# schematic.net
KiCad netlist of a schematic drawn in Altium Designer
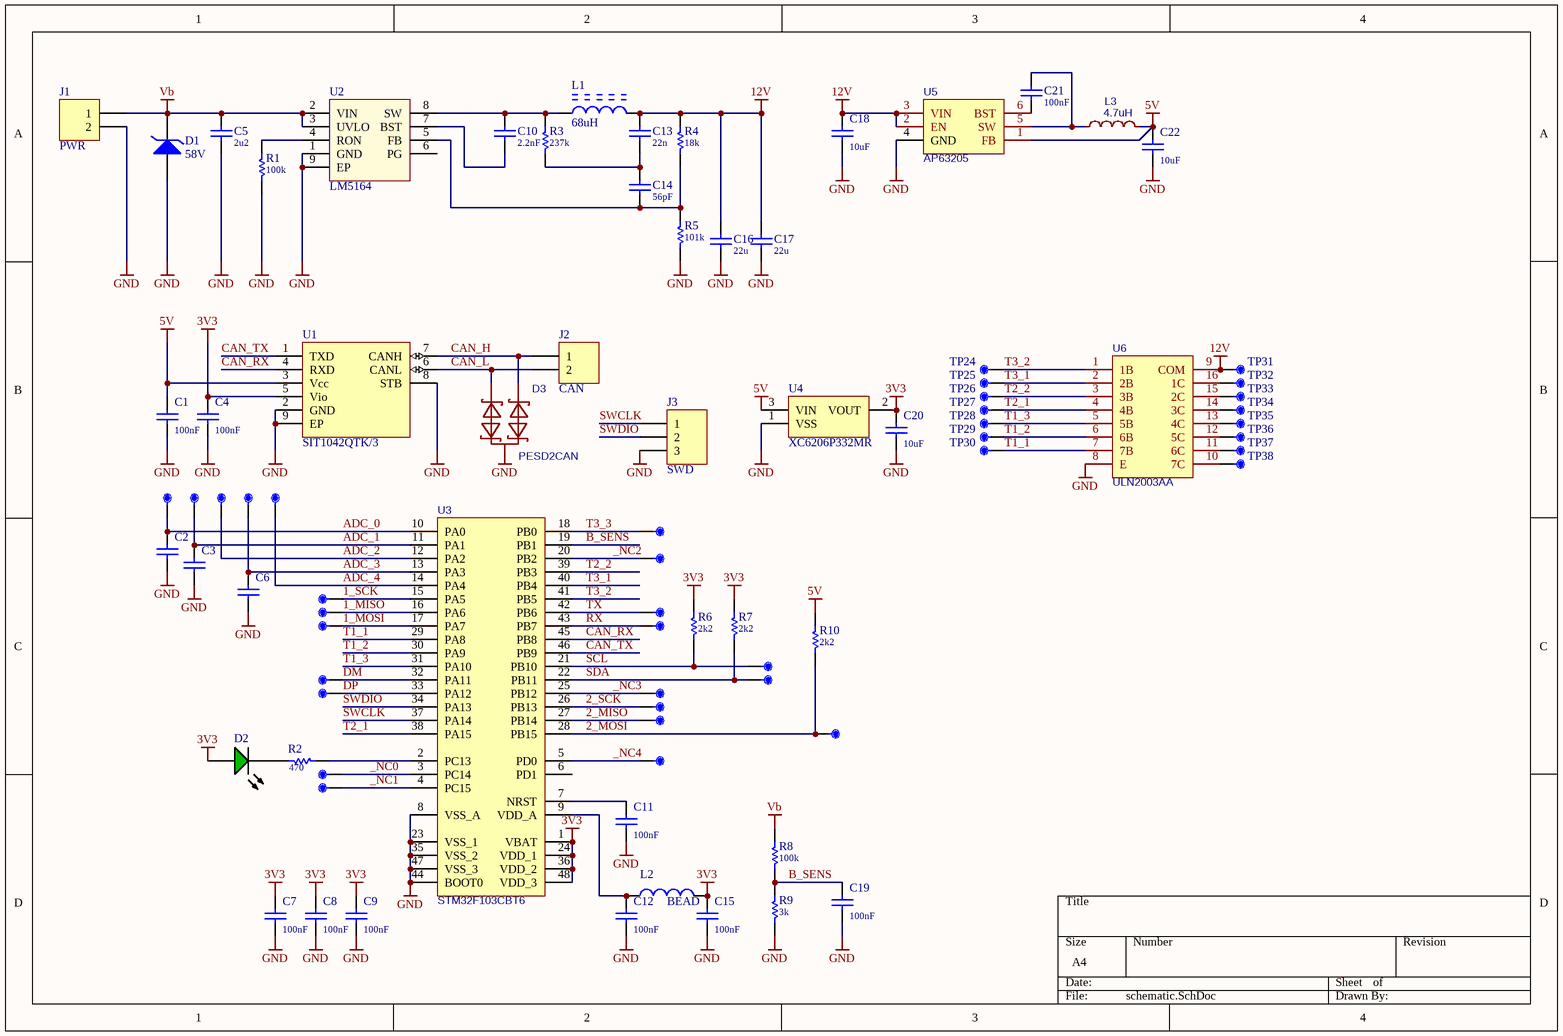
[diagram p0: schematic.SchDoc]

(export (version "E")
  (design (tool "Eeschema 10.0.6"))
  (components
    (comp (ref "C1")
      (value "100nF")
      (footprint "C0402")
      (description "100nF 50V 0402")
      (libsource (lib "Miscellaneous Devices") (part "CAP"))
    )
    (comp (ref "C2")
      (value "100nF")
      (footprint "C0402")
      (description "100nF 50V 0402")
      (libsource (lib "Miscellaneous Devices") (part "CAP"))
    )
    (comp (ref "C3")
      (value "100nF")
      (footprint "C0402")
      (description "100nF 50V 0402")
      (libsource (lib "Miscellaneous Devices") (part "CAP"))
    )
    (comp (ref "C4")
      (value "100nF")
      (footprint "C0402")
      (description "100nF 50V 0402")
      (libsource (lib "Miscellaneous Devices") (part "CAP"))
    )
    (comp (ref "C5")
      (value "2u2")
      (footprint "C1210")
      (description "2.2uF 100V 1210")
      (libsource (lib "Miscellaneous Devices") (part "CAP"))
    )
    (comp (ref "C6")
      (value "100nF")
      (footprint "C0402")
      (description "100nF 50V 0402")
      (libsource (lib "Miscellaneous Devices") (part "CAP"))
    )
    (comp (ref "C7")
      (value "100nF")
      (footprint "C0402")
      (description "100nF 50V 0402")
      (libsource (lib "Miscellaneous Devices") (part "CAP"))
    )
    (comp (ref "C8")
      (value "100nF")
      (footprint "C0402")
      (description "100nF 50V 0402")
      (libsource (lib "Miscellaneous Devices") (part "CAP"))
    )
    (comp (ref "C9")
      (value "100nF")
      (footprint "C0402")
      (description "100nF 50V 0402")
      (libsource (lib "Miscellaneous Devices") (part "CAP"))
    )
    (comp (ref "C10")
      (value "2.2nF")
      (footprint "C0603")
      (description "2.2nF 50V 0603")
      (libsource (lib "Miscellaneous Devices") (part "CAP"))
    )
    (comp (ref "C11")
      (value "100nF")
      (footprint "C0402")
      (description "100nF 50V 0402")
      (libsource (lib "Miscellaneous Devices") (part "CAP"))
    )
    (comp (ref "C12")
      (value "100nF")
      (footprint "C0402")
      (description "100nF 50V 0402")
      (libsource (lib "Miscellaneous Devices") (part "CAP"))
    )
    (comp (ref "C13")
      (value "22n")
      (footprint "C0603")
      (description "2.2nF 0603")
      (libsource (lib "Miscellaneous Devices") (part "CAP"))
    )
    (comp (ref "C14")
      (value "56pF")
      (footprint "C0603")
      (description "56pF 0603")
      (libsource (lib "Miscellaneous Devices") (part "CAP"))
    )
    (comp (ref "C15")
      (value "100nF")
      (footprint "C0402")
      (description "100nF 50V 0402")
      (libsource (lib "Miscellaneous Devices") (part "CAP"))
    )
    (comp (ref "C16")
      (value "22u")
      (footprint "C1210")
      (description "22u 35V 1210")
      (libsource (lib "Miscellaneous Devices") (part "CAP"))
    )
    (comp (ref "C17")
      (value "22u")
      (footprint "C1210")
      (description "22u 35V 1210")
      (libsource (lib "Miscellaneous Devices") (part "CAP"))
    )
    (comp (ref "C18")
      (value "10uF")
      (footprint "C1206")
      (description "10uf 50V 1206")
      (fields (field (name "LCSC PART NUMBER") "C89632"))
      (libsource (lib "Miscellaneous Devices") (part "CAP"))
    )
    (comp (ref "C19")
      (value "100nF")
      (footprint "C0402")
      (description "100nF 50V 0402")
      (libsource (lib "Miscellaneous Devices") (part "CAP"))
    )
    (comp (ref "C20")
      (value "10uF")
      (footprint "C0603")
      (description "10uf 50V 1206")
      (libsource (lib "Miscellaneous Devices") (part "CAP"))
    )
    (comp (ref "C21")
      (value "100nF")
      (footprint "C0402")
      (description "100nF 50V 0402")
      (libsource (lib "Miscellaneous Devices") (part "CAP"))
    )
    (comp (ref "C22")
      (value "10uF")
      (footprint "C1206")
      (description "10uf 50V 1206")
      (fields (field (name "LCSC PART NUMBER") "C89632"))
      (libsource (lib "Miscellaneous Devices") (part "CAP"))
    )
    (comp (ref "D1")
      (value "58V")
      (footprint "SMA")
      (description "SMAJ58A")
      (fields (field (name "LCSC PART NUMBER") "C693617"))
      (libsource (lib "Miscellaneous Devices") (part "NCP51460SN33T1G"))
    )
    (comp (ref "D2")
      (value "GRN")
      (footprint "LED-0603-GRN")
      (description "LED 0603 GRN")
      (libsource (lib "Miscellaneous Devices") (part "LED-0603-GREEN"))
    )
    (comp (ref "D3")
      (value "PESD2CAN")
      (footprint "SOT-23")
      (fields (field (name "LCSC PART NUMBER") "C5261081"))
      (libsource (lib "Miscellaneous Devices") (part "CDSOT23-SM712"))
    )
    (comp (ref "J1") (value "PWR") (footprint "HDR-1X2") (libsource (lib "Schlib1") (part "Header 2")))
    (comp (ref "J2") (value "CAN") (footprint "HDR-1X2") (libsource (lib "") (part "Header 2_1")))
    (comp (ref "J3")
      (value "SWD")
      (footprint "HDR-1x3-P1.25")
      (libsource (lib "Miscellaneous Devices") (part "Header 3"))
    )
    (comp (ref "L1")
      (value "68uH")
      (footprint "L0605-POWER")
      (description "PSPMAA0605H-680M-IGF")
      (libsource (lib "Miscellaneous Devices") (part "SRN3015-100M"))
    )
    (comp (ref "L2")
      (value "BEAD")
      (footprint "L0402")
      (description "BEAD 0402")
      (libsource (lib "Miscellaneous Devices") (part "BLM18AG601SN1D"))
    )
    (comp (ref "L3")
      (value "4.7uH")
      (footprint "IND-SMD_L4.4-W4.2")
      (fields (field (name "LCSC PART NUMBER") "C167208"))
      (libsource (lib "altium-import") (part "root_0_4.7uH_"))
    )
    (comp (ref "R1")
      (value "100k")
      (footprint "R0603")
      (description "100k 0603")
      (libsource (lib "Miscellaneous Devices") (part "RES"))
    )
    (comp (ref "R2")
      (value "470")
      (footprint "R0402")
      (description "470 0603")
      (libsource (lib "Miscellaneous Devices") (part "RES"))
    )
    (comp (ref "R3")
      (value "237k")
      (footprint "R0603")
      (description "237k 0603")
      (libsource (lib "Miscellaneous Devices") (part "RES"))
    )
    (comp (ref "R4")
      (value "18k")
      (footprint "R0603")
      (description "18k 1% 0603")
      (libsource (lib "Miscellaneous Devices") (part "RES"))
    )
    (comp (ref "R5")
      (value "101k")
      (footprint "R0603")
      (description "101k 0603")
      (libsource (lib "Miscellaneous Devices") (part "RES"))
    )
    (comp (ref "R6") (value "2k2") (footprint "R0402") (libsource (lib "Miscellaneous Devices") (part "RES")))
    (comp (ref "R7") (value "2k2") (footprint "R0402") (libsource (lib "Miscellaneous Devices") (part "RES")))
    (comp (ref "R8")
      (value "100k")
      (footprint "R0603")
      (libsource (lib "Miscellaneous Devices") (part "RES"))
    )
    (comp (ref "R9") (value "3k") (footprint "R0603") (libsource (lib "Miscellaneous Devices") (part "RES")))
    (comp (ref "R10")
      (value "2k2")
      (footprint "R0402")
      (libsource (lib "Miscellaneous Devices") (part "RES"))
    )
    (comp (ref "TP1")
      (value "~")
      (footprint "TP_THT")
      (libsource (lib "Miscellaneous Devices") (part "TP_Dup1"))
    )
    (comp (ref "TP2")
      (value "~")
      (footprint "TP_THT")
      (libsource (lib "Miscellaneous Devices") (part "TP_Dup1"))
    )
    (comp (ref "TP3")
      (value "~")
      (footprint "TP_THT")
      (libsource (lib "Miscellaneous Devices") (part "TP_Dup1"))
    )
    (comp (ref "TP4")
      (value "~")
      (footprint "TP_THT")
      (libsource (lib "Miscellaneous Devices") (part "TP_Dup1"))
    )
    (comp (ref "TP5")
      (value "~")
      (footprint "TP_THT")
      (libsource (lib "Miscellaneous Devices") (part "TP_Dup1"))
    )
    (comp (ref "TP6")
      (value "~")
      (footprint "TP_THT")
      (libsource (lib "Miscellaneous Devices") (part "TP_Dup1"))
    )
    (comp (ref "TP7")
      (value "~")
      (footprint "TP_THT")
      (libsource (lib "Miscellaneous Devices") (part "TP_Dup1"))
    )
    (comp (ref "TP8")
      (value "~")
      (footprint "TP_THT")
      (libsource (lib "Miscellaneous Devices") (part "TP_Dup1"))
    )
    (comp (ref "TP9")
      (value "~")
      (footprint "TP_THT")
      (libsource (lib "Miscellaneous Devices") (part "TP_Dup1"))
    )
    (comp (ref "TP10")
      (value "~")
      (footprint "TP_THT")
      (libsource (lib "Miscellaneous Devices") (part "TP_Dup1"))
    )
    (comp (ref "TP11")
      (value "~")
      (footprint "TP_THT")
      (libsource (lib "Miscellaneous Devices") (part "TP_Dup1"))
    )
    (comp (ref "TP12")
      (value "~")
      (footprint "TP_THT")
      (libsource (lib "Miscellaneous Devices") (part "TP_Dup1"))
    )
    (comp (ref "TP13")
      (value "~")
      (footprint "TP_THT")
      (libsource (lib "Miscellaneous Devices") (part "TP_Dup1"))
    )
    (comp (ref "TP14")
      (value "~")
      (footprint "TP_THT")
      (libsource (lib "Miscellaneous Devices") (part "TP_Dup1"))
    )
    (comp (ref "TP15")
      (value "~")
      (footprint "TP_THT")
      (libsource (lib "Miscellaneous Devices") (part "TP_Dup1"))
    )
    (comp (ref "TP16")
      (value "~")
      (footprint "TP_THT")
      (libsource (lib "Miscellaneous Devices") (part "TP_Dup1"))
    )
    (comp (ref "TP17")
      (value "~")
      (footprint "TP_THT")
      (libsource (lib "Miscellaneous Devices") (part "TP_Dup1"))
    )
    (comp (ref "TP18")
      (value "~")
      (footprint "TP_THT")
      (libsource (lib "Miscellaneous Devices") (part "TP_Dup1"))
    )
    (comp (ref "TP19")
      (value "~")
      (footprint "TP_THT")
      (libsource (lib "Miscellaneous Devices") (part "TP_Dup1"))
    )
    (comp (ref "TP20")
      (value "~")
      (footprint "TP_THT")
      (libsource (lib "Miscellaneous Devices") (part "TP_Dup1"))
    )
    (comp (ref "TP21")
      (value "~")
      (footprint "TP_THT")
      (libsource (lib "Miscellaneous Devices") (part "TP_Dup1"))
    )
    (comp (ref "TP22")
      (value "~")
      (footprint "TP_THT")
      (libsource (lib "Miscellaneous Devices") (part "TP_Dup1"))
    )
    (comp (ref "TP23")
      (value "~")
      (footprint "TP_THT")
      (libsource (lib "Miscellaneous Devices") (part "TP_Dup1"))
    )
    (comp (ref "TP24")
      (value "~")
      (footprint "TP_THT")
      (libsource (lib "Miscellaneous Devices") (part "TP_Dup1"))
    )
    (comp (ref "TP25")
      (value "~")
      (footprint "TP_THT")
      (libsource (lib "Miscellaneous Devices") (part "TP_Dup1"))
    )
    (comp (ref "TP26")
      (value "~")
      (footprint "TP_THT")
      (libsource (lib "Miscellaneous Devices") (part "TP_Dup1"))
    )
    (comp (ref "TP27")
      (value "~")
      (footprint "TP_THT")
      (libsource (lib "Miscellaneous Devices") (part "TP_Dup1"))
    )
    (comp (ref "TP28")
      (value "~")
      (footprint "TP_THT")
      (libsource (lib "Miscellaneous Devices") (part "TP_Dup1"))
    )
    (comp (ref "TP29")
      (value "~")
      (footprint "TP_THT")
      (libsource (lib "Miscellaneous Devices") (part "TP_Dup1"))
    )
    (comp (ref "TP30")
      (value "~")
      (footprint "TP_THT")
      (libsource (lib "Miscellaneous Devices") (part "TP_Dup1"))
    )
    (comp (ref "TP31")
      (value "~")
      (footprint "TP_THT")
      (libsource (lib "Miscellaneous Devices") (part "TP_Dup1"))
    )
    (comp (ref "TP32")
      (value "~")
      (footprint "TP_THT")
      (libsource (lib "Miscellaneous Devices") (part "TP_Dup1"))
    )
    (comp (ref "TP33")
      (value "~")
      (footprint "TP_THT")
      (libsource (lib "Miscellaneous Devices") (part "TP_Dup1"))
    )
    (comp (ref "TP34")
      (value "~")
      (footprint "TP_THT")
      (libsource (lib "Miscellaneous Devices") (part "TP_Dup1"))
    )
    (comp (ref "TP35")
      (value "~")
      (footprint "TP_THT")
      (libsource (lib "Miscellaneous Devices") (part "TP_Dup1"))
    )
    (comp (ref "TP36")
      (value "~")
      (footprint "TP_THT")
      (libsource (lib "Miscellaneous Devices") (part "TP_Dup1"))
    )
    (comp (ref "TP37")
      (value "~")
      (footprint "TP_THT")
      (libsource (lib "Miscellaneous Devices") (part "TP_Dup1"))
    )
    (comp (ref "TP38")
      (value "~")
      (footprint "TP_THT")
      (libsource (lib "Miscellaneous Devices") (part "TP_Dup1"))
    )
    (comp (ref "U1")
      (value "SIT1042QTK/3")
      (footprint "DFN8_3X3_P065")
      (description "IC INTERFACE CAN")
      (libsource (lib "Miscellaneous Devices") (part "LTC2875"))
    )
    (comp (ref "U2") (value "LM5164") (footprint "PowerSOIC-8") (libsource (lib "Schlib2") (part "LM5164")))
    (comp (ref "U3")
      (value "STM32F103CBT6")
      (footprint "LQFP-48")
      (libsource (lib "Schlib1") (part "STM32F103CBT6"))
    )
    (comp (ref "U4")
      (value "XC6206P332MR")
      (footprint "SOT-23")
      (libsource (lib "Schlib1") (part "Component_4_1"))
    )
    (comp (ref "U5")
      (value "AP63205")
      (footprint "SOT-23-6")
      (fields (field (name "LCSC PART NUMBER") "C780769"))
      (libsource (lib "Schlib1") (part "AP63203WU-7"))
    )
    (comp (ref "U6") (value "ULN2003AA") (footprint "SOIC-16") (libsource (lib "Schlib1") (part "ULN2003A")))
  )
  (nets
    (net (code "1") (name "/1_MISO") (class "Default")
      (node (ref "TP7") (pin "1") (pinfunction "1_1") (pintype "passive"))
      (node (ref "U3") (pin "16") (pinfunction "PA6_16") (pintype "passive"))
    )
    (net (code "2") (name "/1_MOSI") (class "Default")
      (node (ref "TP8") (pin "1") (pinfunction "1_1") (pintype "passive"))
      (node (ref "U3") (pin "17") (pinfunction "PA7_17") (pintype "passive"))
    )
    (net (code "3") (name "/1_SCK") (class "Default")
      (node (ref "TP6") (pin "1") (pinfunction "1_1") (pintype "passive"))
      (node (ref "U3") (pin "15") (pinfunction "PA5_15") (pintype "passive"))
    )
    (net (code "4") (name "/2_MISO") (class "Default")
      (node (ref "TP19") (pin "1") (pinfunction "1_1") (pintype "passive"))
      (node (ref "U3") (pin "27") (pinfunction "PB14_27") (pintype "passive"))
    )
    (net (code "5") (name "/2_MOSI") (class "Default")
      (node (ref "R10") (pin "1") (pinfunction "1_1") (pintype "passive"))
      (node (ref "TP23") (pin "1") (pinfunction "1_1") (pintype "passive"))
      (node (ref "U3") (pin "28") (pinfunction "PB15_28") (pintype "passive"))
    )
    (net (code "6") (name "/2_SCK") (class "Default")
      (node (ref "TP18") (pin "1") (pinfunction "1_1") (pintype "passive"))
      (node (ref "U3") (pin "26") (pinfunction "PB13_26") (pintype "passive"))
    )
    (net (code "7") (name "/ADC_0") (class "Default")
      (node (ref "C2") (pin "2") (pinfunction "2_2") (pintype "passive"))
      (node (ref "TP1") (pin "1") (pinfunction "1_1") (pintype "passive"))
      (node (ref "U3") (pin "10") (pinfunction "PA0_10") (pintype "passive"))
    )
    (net (code "8") (name "/ADC_1") (class "Default")
      (node (ref "C3") (pin "2") (pinfunction "2_2") (pintype "passive"))
      (node (ref "TP2") (pin "1") (pinfunction "1_1") (pintype "passive"))
      (node (ref "U3") (pin "11") (pinfunction "PA1_11") (pintype "passive"))
    )
    (net (code "9") (name "/ADC_2") (class "Default")
      (node (ref "TP3") (pin "1") (pinfunction "1_1") (pintype "passive"))
      (node (ref "U3") (pin "12") (pinfunction "PA2_12") (pintype "passive"))
    )
    (net (code "10") (name "/ADC_3") (class "Default")
      (node (ref "C6") (pin "2") (pinfunction "2_2") (pintype "passive"))
      (node (ref "TP4") (pin "1") (pinfunction "1_1") (pintype "passive"))
      (node (ref "U3") (pin "13") (pinfunction "PA3_13") (pintype "passive"))
    )
    (net (code "11") (name "/ADC_4") (class "Default")
      (node (ref "TP5") (pin "1") (pinfunction "1_1") (pintype "passive"))
      (node (ref "U3") (pin "14") (pinfunction "PA4_14") (pintype "passive"))
    )
    (net (code "12") (name "/B_SENS") (class "Default")
      (node (ref "C19") (pin "2") (pinfunction "2_2") (pintype "passive"))
      (node (ref "R8") (pin "1") (pinfunction "1_1") (pintype "passive"))
      (node (ref "R9") (pin "2") (pinfunction "2_2") (pintype "passive"))
      (node (ref "U3") (pin "19") (pinfunction "PB1_19") (pintype "passive"))
    )
    (net (code "13") (name "/CAN_H") (class "Default")
      (node (ref "D3") (pin "2") (pinfunction "2_2") (pintype "passive"))
      (node (ref "J2") (pin "1") (pinfunction "1_1") (pintype "passive"))
      (node (ref "U1") (pin "7") (pinfunction "CANH_7") (pintype "bidirectional"))
    )
    (net (code "14") (name "/CAN_L") (class "Default")
      (node (ref "D3") (pin "1") (pinfunction "1_1") (pintype "passive"))
      (node (ref "J2") (pin "2") (pinfunction "2_2") (pintype "passive"))
      (node (ref "U1") (pin "6") (pinfunction "CANL_6") (pintype "bidirectional"))
    )
    (net (code "15") (name "/CAN_RX") (class "Default")
      (node (ref "U1") (pin "4") (pinfunction "RXD_4") (pintype "passive"))
      (node (ref "U3") (pin "45") (pinfunction "PB8_45") (pintype "passive"))
    )
    (net (code "16") (name "/CAN_TX") (class "Default")
      (node (ref "U1") (pin "1") (pinfunction "TXD_1") (pintype "passive"))
      (node (ref "U3") (pin "46") (pinfunction "PB9_46") (pintype "passive"))
    )
    (net (code "17") (name "/DM") (class "Default")
      (node (ref "TP9") (pin "1") (pinfunction "1_1") (pintype "passive"))
      (node (ref "U3") (pin "32") (pinfunction "PA11_32") (pintype "passive"))
    )
    (net (code "18") (name "/DP") (class "Default")
      (node (ref "TP10") (pin "1") (pinfunction "1_1") (pintype "passive"))
      (node (ref "U3") (pin "33") (pinfunction "PA12_33") (pintype "passive"))
    )
    (net (code "19") (name "/RX") (class "Default")
      (node (ref "TP16") (pin "1") (pinfunction "1_1") (pintype "passive"))
      (node (ref "U3") (pin "43") (pinfunction "PB7_43") (pintype "passive"))
    )
    (net (code "20") (name "/SCL") (class "Default")
      (node (ref "R6") (pin "1") (pinfunction "1_1") (pintype "passive"))
      (node (ref "TP21") (pin "1") (pinfunction "1_1") (pintype "passive"))
      (node (ref "U3") (pin "21") (pinfunction "PB10_21") (pintype "passive"))
    )
    (net (code "21") (name "/SDA") (class "Default")
      (node (ref "R7") (pin "1") (pinfunction "1_1") (pintype "passive"))
      (node (ref "TP22") (pin "1") (pinfunction "1_1") (pintype "passive"))
      (node (ref "U3") (pin "22") (pinfunction "PB11_22") (pintype "passive"))
    )
    (net (code "22") (name "/SWCLK") (class "Default")
      (node (ref "J3") (pin "1") (pinfunction "1_1") (pintype "passive"))
      (node (ref "U3") (pin "37") (pinfunction "PA14_37") (pintype "passive"))
    )
    (net (code "23") (name "/SWDIO") (class "Default")
      (node (ref "J3") (pin "2") (pinfunction "2_2") (pintype "passive"))
      (node (ref "U3") (pin "34") (pinfunction "PA13_34") (pintype "passive"))
    )
    (net (code "24") (name "/T1_1") (class "Default")
      (node (ref "TP30") (pin "1") (pinfunction "1_1") (pintype "passive"))
      (node (ref "U3") (pin "29") (pinfunction "PA8_29") (pintype "passive"))
      (node (ref "U6") (pin "7") (pinfunction "7B_7") (pintype "passive"))
    )
    (net (code "25") (name "/T1_2") (class "Default")
      (node (ref "TP29") (pin "1") (pinfunction "1_1") (pintype "passive"))
      (node (ref "U3") (pin "30") (pinfunction "PA9_30") (pintype "passive"))
      (node (ref "U6") (pin "6") (pinfunction "6B_6") (pintype "passive"))
    )
    (net (code "26") (name "/T1_3") (class "Default")
      (node (ref "TP28") (pin "1") (pinfunction "1_1") (pintype "passive"))
      (node (ref "U3") (pin "31") (pinfunction "PA10_31") (pintype "passive"))
      (node (ref "U6") (pin "5") (pinfunction "5B_5") (pintype "passive"))
    )
    (net (code "27") (name "/T2_1") (class "Default")
      (node (ref "TP27") (pin "1") (pinfunction "1_1") (pintype "passive"))
      (node (ref "U3") (pin "38") (pinfunction "PA15_38") (pintype "passive"))
      (node (ref "U6") (pin "4") (pinfunction "4B_4") (pintype "passive"))
    )
    (net (code "28") (name "/T2_2") (class "Default")
      (node (ref "TP26") (pin "1") (pinfunction "1_1") (pintype "passive"))
      (node (ref "U3") (pin "39") (pinfunction "PB3_39") (pintype "passive"))
      (node (ref "U6") (pin "3") (pinfunction "3B_3") (pintype "passive"))
    )
    (net (code "29") (name "/T3_1") (class "Default")
      (node (ref "TP25") (pin "1") (pinfunction "1_1") (pintype "passive"))
      (node (ref "U3") (pin "40") (pinfunction "PB4_40") (pintype "passive"))
      (node (ref "U6") (pin "2") (pinfunction "2B_2") (pintype "passive"))
    )
    (net (code "30") (name "/T3_2") (class "Default")
      (node (ref "TP24") (pin "1") (pinfunction "1_1") (pintype "passive"))
      (node (ref "U3") (pin "41") (pinfunction "PB5_41") (pintype "passive"))
      (node (ref "U6") (pin "1") (pinfunction "1B_1") (pintype "passive"))
    )
    (net (code "31") (name "/T3_3") (class "Default")
      (node (ref "TP13") (pin "1") (pinfunction "1_1") (pintype "passive"))
      (node (ref "U3") (pin "18") (pinfunction "PB0_18") (pintype "passive"))
    )
    (net (code "32") (name "/TX") (class "Default")
      (node (ref "TP15") (pin "1") (pinfunction "1_1") (pintype "passive"))
      (node (ref "U3") (pin "42") (pinfunction "PB6_42") (pintype "passive"))
    )
    (net (code "33") (name "/_NC0") (class "Default")
      (node (ref "TP11") (pin "1") (pinfunction "1_1") (pintype "passive"))
      (node (ref "U3") (pin "3") (pinfunction "PC14_3") (pintype "passive"))
    )
    (net (code "34") (name "/_NC1") (class "Default")
      (node (ref "TP12") (pin "1") (pinfunction "1_1") (pintype "passive"))
      (node (ref "U3") (pin "4") (pinfunction "PC15_4") (pintype "passive"))
    )
    (net (code "35") (name "/_NC2") (class "Default")
      (node (ref "TP14") (pin "1") (pinfunction "1_1") (pintype "passive"))
      (node (ref "U3") (pin "20") (pinfunction "PB2_20") (pintype "passive"))
    )
    (net (code "36") (name "/_NC3") (class "Default")
      (node (ref "TP17") (pin "1") (pinfunction "1_1") (pintype "passive"))
      (node (ref "U3") (pin "25") (pinfunction "PB12_25") (pintype "passive"))
    )
    (net (code "37") (name "/_NC4") (class "Default")
      (node (ref "TP20") (pin "1") (pinfunction "1_1") (pintype "passive"))
      (node (ref "U3") (pin "5") (pinfunction "PD0_5") (pintype "passive"))
    )
    (net (code "38") (name "3V3") (class "Default")
      (node (ref "C15") (pin "2") (pinfunction "2_2") (pintype "passive"))
      (node (ref "C20") (pin "2") (pinfunction "2_2") (pintype "passive"))
      (node (ref "C4") (pin "2") (pinfunction "2_2") (pintype "passive"))
      (node (ref "C7") (pin "2") (pinfunction "2_2") (pintype "passive"))
      (node (ref "C8") (pin "2") (pinfunction "2_2") (pintype "passive"))
      (node (ref "C9") (pin "2") (pinfunction "2_2") (pintype "passive"))
      (node (ref "D2") (pin "1") (pinfunction "A_1") (pintype "passive"))
      (node (ref "L2") (pin "1") (pinfunction "1_1") (pintype "passive"))
      (node (ref "R6") (pin "2") (pinfunction "2_2") (pintype "passive"))
      (node (ref "R7") (pin "2") (pinfunction "2_2") (pintype "passive"))
      (node (ref "U1") (pin "5") (pinfunction "Vio_5") (pintype "passive"))
      (node (ref "U3") (pin "1") (pinfunction "VBAT_1") (pintype "passive"))
      (node (ref "U3") (pin "24") (pinfunction "VDD_1_24") (pintype "passive"))
      (node (ref "U3") (pin "36") (pinfunction "VDD_2_36") (pintype "passive"))
      (node (ref "U3") (pin "48") (pinfunction "VDD_3_48") (pintype "passive"))
      (node (ref "U4") (pin "2") (pinfunction "VOUT_2") (pintype "passive"))
    )
    (net (code "39") (name "5V") (class "Default")
      (node (ref "C1") (pin "2") (pinfunction "2_2") (pintype "passive"))
      (node (ref "C22") (pin "2") (pinfunction "2_2") (pintype "passive"))
      (node (ref "L3") (pin "2") (pinfunction "2_2") (pintype "passive"))
      (node (ref "R10") (pin "2") (pinfunction "2_2") (pintype "passive"))
      (node (ref "U1") (pin "3") (pinfunction "Vcc_3") (pintype "passive"))
      (node (ref "U4") (pin "3") (pinfunction "VIN_3") (pintype "passive"))
      (node (ref "U5") (pin "1") (pinfunction "FB_1") (pintype "passive"))
    )
    (net (code "40") (name "12V") (class "Default")
      (node (ref "C13") (pin "2") (pinfunction "2_2") (pintype "passive"))
      (node (ref "C16") (pin "2") (pinfunction "2_2") (pintype "passive"))
      (node (ref "C17") (pin "2") (pinfunction "2_2") (pintype "passive"))
      (node (ref "C18") (pin "2") (pinfunction "2_2") (pintype "passive"))
      (node (ref "L1") (pin "2") (pinfunction "2_2") (pintype "passive"))
      (node (ref "R4") (pin "1") (pinfunction "1_1") (pintype "passive"))
      (node (ref "TP31") (pin "1") (pinfunction "1_1") (pintype "passive"))
      (node (ref "U5") (pin "2") (pinfunction "EN_2") (pintype "passive"))
      (node (ref "U5") (pin "3") (pinfunction "VIN_3") (pintype "passive"))
      (node (ref "U6") (pin "9") (pinfunction "COM_9") (pintype "passive"))
    )
    (net (code "41") (name "GND") (class "Default")
      (node (ref "C1") (pin "1") (pinfunction "1_1") (pintype "passive"))
      (node (ref "C11") (pin "1") (pinfunction "1_1") (pintype "passive"))
      (node (ref "C12") (pin "1") (pinfunction "1_1") (pintype "passive"))
      (node (ref "C15") (pin "1") (pinfunction "1_1") (pintype "passive"))
      (node (ref "C16") (pin "1") (pinfunction "1_1") (pintype "passive"))
      (node (ref "C17") (pin "1") (pinfunction "1_1") (pintype "passive"))
      (node (ref "C18") (pin "1") (pinfunction "1_1") (pintype "passive"))
      (node (ref "C19") (pin "1") (pinfunction "1_1") (pintype "passive"))
      (node (ref "C2") (pin "1") (pinfunction "1_1") (pintype "passive"))
      (node (ref "C20") (pin "1") (pinfunction "1_1") (pintype "passive"))
      (node (ref "C22") (pin "1") (pinfunction "1_1") (pintype "passive"))
      (node (ref "C3") (pin "1") (pinfunction "1_1") (pintype "passive"))
      (node (ref "C4") (pin "1") (pinfunction "1_1") (pintype "passive"))
      (node (ref "C5") (pin "1") (pinfunction "1_1") (pintype "passive"))
      (node (ref "C6") (pin "1") (pinfunction "1_1") (pintype "passive"))
      (node (ref "C7") (pin "1") (pinfunction "1_1") (pintype "passive"))
      (node (ref "C8") (pin "1") (pinfunction "1_1") (pintype "passive"))
      (node (ref "C9") (pin "1") (pinfunction "1_1") (pintype "passive"))
      (node (ref "D1") (pin "1") (pinfunction "-_1") (pintype "passive"))
      (node (ref "D3") (pin "3") (pinfunction "3_3") (pintype "passive"))
      (node (ref "J1") (pin "2") (pinfunction "2_2") (pintype "passive"))
      (node (ref "J3") (pin "3") (pinfunction "3_3") (pintype "passive"))
      (node (ref "R1") (pin "2") (pinfunction "2_2") (pintype "passive"))
      (node (ref "R5") (pin "2") (pinfunction "2_2") (pintype "passive"))
      (node (ref "R9") (pin "1") (pinfunction "1_1") (pintype "passive"))
      (node (ref "U1") (pin "2") (pinfunction "GND_2") (pintype "passive"))
      (node (ref "U1") (pin "8") (pinfunction "STB_8") (pintype "passive"))
      (node (ref "U1") (pin "9") (pinfunction "EP_9") (pintype "passive"))
      (node (ref "U2") (pin "1") (pinfunction "GND_1") (pintype "power_in"))
      (node (ref "U2") (pin "9") (pinfunction "EP_9") (pintype "passive"))
      (node (ref "U3") (pin "23") (pinfunction "VSS_1_23") (pintype "passive"))
      (node (ref "U3") (pin "35") (pinfunction "VSS_2_35") (pintype "passive"))
      (node (ref "U3") (pin "44") (pinfunction "BOOT0_44") (pintype "passive"))
      (node (ref "U3") (pin "47") (pinfunction "VSS_3_47") (pintype "passive"))
      (node (ref "U3") (pin "8") (pinfunction "VSS_A_8") (pintype "passive"))
      (node (ref "U4") (pin "1") (pinfunction "VSS_1") (pintype "passive"))
      (node (ref "U5") (pin "4") (pinfunction "GND_4") (pintype "passive"))
      (node (ref "U6") (pin "8") (pinfunction "E_8") (pintype "passive"))
    )
    (net (code "42") (name "Net-(C13-Pad1)") (class "Default")
      (node (ref "C13") (pin "1") (pinfunction "1_1") (pintype "passive"))
      (node (ref "C14") (pin "2") (pinfunction "2_2") (pintype "passive"))
      (node (ref "R3") (pin "2") (pinfunction "2_2") (pintype "passive"))
    )
    (net (code "43") (name "Net-(D2-K)") (class "Default")
      (node (ref "D2") (pin "2") (pinfunction "K_2") (pintype "passive"))
      (node (ref "R2") (pin "1") (pinfunction "1_1") (pintype "passive"))
    )
    (net (code "44") (name "Net-(U2-BST)") (class "Default")
      (node (ref "C10") (pin "1") (pinfunction "1_1") (pintype "passive"))
      (node (ref "U2") (pin "7") (pinfunction "BST_7") (pintype "passive"))
    )
    (net (code "45") (name "Net-(U2-FB)") (class "Default")
      (node (ref "C14") (pin "1") (pinfunction "1_1") (pintype "passive"))
      (node (ref "R4") (pin "2") (pinfunction "2_2") (pintype "passive"))
      (node (ref "R5") (pin "1") (pinfunction "1_1") (pintype "passive"))
      (node (ref "U2") (pin "5") (pinfunction "FB_5") (pintype "power_in"))
    )
    (net (code "46") (name "Net-(U2-RON)") (class "Default")
      (node (ref "R1") (pin "1") (pinfunction "1_1") (pintype "passive"))
      (node (ref "U2") (pin "4") (pinfunction "RON_4") (pintype "power_in"))
    )
    (net (code "47") (name "Net-(U2-SW)") (class "Default")
      (node (ref "C10") (pin "2") (pinfunction "2_2") (pintype "passive"))
      (node (ref "L1") (pin "1") (pinfunction "1_1") (pintype "passive"))
      (node (ref "R3") (pin "1") (pinfunction "1_1") (pintype "passive"))
      (node (ref "U2") (pin "8") (pinfunction "SW_8") (pintype "power_in"))
    )
    (net (code "48") (name "Net-(U3-NRST)") (class "Default")
      (node (ref "C11") (pin "2") (pinfunction "2_2") (pintype "passive"))
      (node (ref "U3") (pin "7") (pinfunction "NRST_7") (pintype "passive"))
    )
    (net (code "49") (name "Net-(U3-PC13)") (class "Default")
      (node (ref "R2") (pin "2") (pinfunction "2_2") (pintype "passive"))
      (node (ref "U3") (pin "2") (pinfunction "PC13_2") (pintype "passive"))
    )
    (net (code "50") (name "Net-(U3-VDD_A)") (class "Default")
      (node (ref "C12") (pin "2") (pinfunction "2_2") (pintype "passive"))
      (node (ref "L2") (pin "2") (pinfunction "2_2") (pintype "passive"))
      (node (ref "U3") (pin "9") (pinfunction "VDD_A_9") (pintype "passive"))
    )
    (net (code "51") (name "Net-(U5-BST)") (class "Default")
      (node (ref "C21") (pin "1") (pinfunction "1_1") (pintype "passive"))
      (node (ref "U5") (pin "6") (pinfunction "BST_6") (pintype "passive"))
    )
    (net (code "52") (name "Net-(U5-SW)") (class "Default")
      (node (ref "C21") (pin "2") (pinfunction "2_2") (pintype "passive"))
      (node (ref "L3") (pin "1") (pinfunction "1_1") (pintype "passive"))
      (node (ref "U5") (pin "5") (pinfunction "SW_5") (pintype "passive"))
    )
    (net (code "53") (name "Net-(U6-1C)") (class "Default")
      (node (ref "TP32") (pin "1") (pinfunction "1_1") (pintype "passive"))
      (node (ref "U6") (pin "16") (pinfunction "1C_16") (pintype "passive"))
    )
    (net (code "54") (name "Net-(U6-2C)") (class "Default")
      (node (ref "TP33") (pin "1") (pinfunction "1_1") (pintype "passive"))
      (node (ref "U6") (pin "15") (pinfunction "2C_15") (pintype "passive"))
    )
    (net (code "55") (name "Net-(U6-3C)") (class "Default")
      (node (ref "TP34") (pin "1") (pinfunction "1_1") (pintype "passive"))
      (node (ref "U6") (pin "14") (pinfunction "3C_14") (pintype "passive"))
    )
    (net (code "56") (name "Net-(U6-4C)") (class "Default")
      (node (ref "TP35") (pin "1") (pinfunction "1_1") (pintype "passive"))
      (node (ref "U6") (pin "13") (pinfunction "4C_13") (pintype "passive"))
    )
    (net (code "57") (name "Net-(U6-5C)") (class "Default")
      (node (ref "TP36") (pin "1") (pinfunction "1_1") (pintype "passive"))
      (node (ref "U6") (pin "12") (pinfunction "5C_12") (pintype "passive"))
    )
    (net (code "58") (name "Net-(U6-6C)") (class "Default")
      (node (ref "TP37") (pin "1") (pinfunction "1_1") (pintype "passive"))
      (node (ref "U6") (pin "11") (pinfunction "6C_11") (pintype "passive"))
    )
    (net (code "59") (name "Net-(U6-7C)") (class "Default")
      (node (ref "TP38") (pin "1") (pinfunction "1_1") (pintype "passive"))
      (node (ref "U6") (pin "10") (pinfunction "7C_10") (pintype "passive"))
    )
    (net (code "60") (name "Vb") (class "Default")
      (node (ref "C5") (pin "2") (pinfunction "2_2") (pintype "passive"))
      (node (ref "D1") (pin "2") (pinfunction "+_2") (pintype "passive"))
      (node (ref "J1") (pin "1") (pinfunction "1_1") (pintype "passive"))
      (node (ref "R8") (pin "2") (pinfunction "2_2") (pintype "passive"))
      (node (ref "U2") (pin "2") (pinfunction "VIN_2") (pintype "power_in"))
      (node (ref "U2") (pin "3") (pinfunction "UVLO_3") (pintype "passive"))
    )
    (net (code "61") (name "unconnected-(U2-PG-Pad6)") (class "Default")
      (node (ref "U2") (pin "6") (pinfunction "PG_6") (pintype "open_collector"))
    )
    (net (code "62") (name "unconnected-(U3-PD1-Pad6)") (class "Default")
      (node (ref "U3") (pin "6") (pinfunction "PD1_6") (pintype "passive"))
    )
  )
)
